# BenWalters_BB.net
KiCad netlist of a schematic drawn in EAGLE
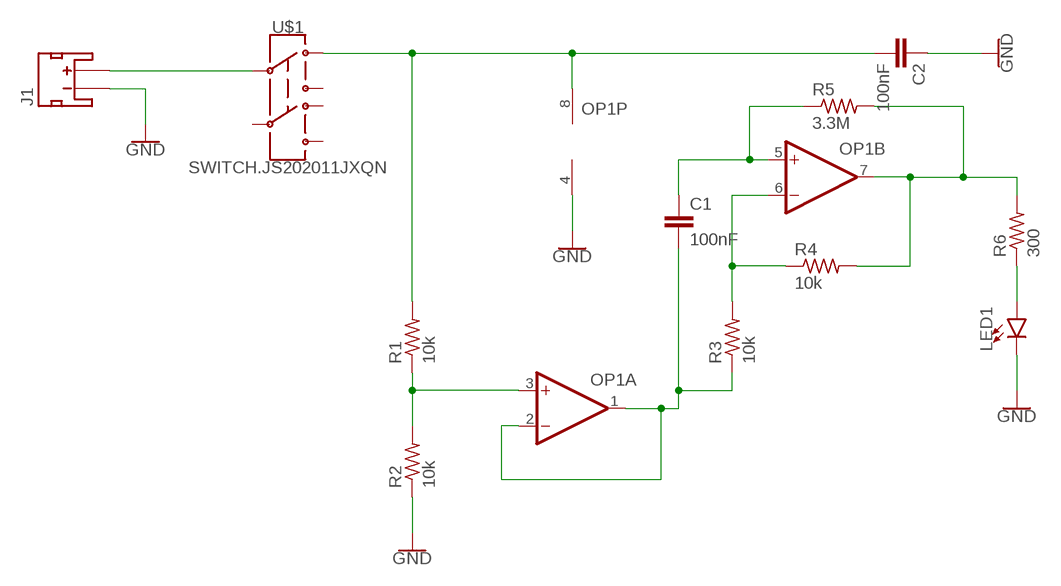
[diagram p0: schematic, sheet 1]

(export (version "E")
  (design (tool "Eeschema 10.0.6"))
  (components
    (comp (ref "C1")
      (value "100nF")
      (footprint "eagle-import:C0805")
      (libsource (lib "eagle-import") (part "CAPACITOR0805"))
    )
    (comp (ref "C2")
      (value "100nF")
      (footprint "eagle-import:C0805")
      (libsource (lib "eagle-import") (part "CAPACITOR0805"))
    )
    (comp (ref "J1")
      (value "3.7V")
      (footprint "eagle-import:JST-2-SMD")
      (libsource (lib "eagle-import") (part "JST_2MM_MALE"))
    )
    (comp (ref "LED1")
      (value "LED3MM")
      (footprint "eagle-import:LED_3MM")
      (libsource (lib "eagle-import") (part "LED3MM"))
    )
    (comp (ref "OP1")
      (value "OP-DUALRM")
      (footprint "eagle-import:MSOP08")
      (fields (field (name "MF") "ALTERA CORPORATION") (field (name "MPN") "AD8607ARMZ-REEL"))
      (libsource (lib "eagle-import") (part "OP-DUALRM"))
    )
    (comp (ref "R1")
      (value "10k")
      (footprint "eagle-import:R0805")
      (libsource (lib "eagle-import") (part "RESISTOR0805"))
    )
    (comp (ref "R2")
      (value "10k")
      (footprint "eagle-import:R0805")
      (libsource (lib "eagle-import") (part "RESISTOR0805"))
    )
    (comp (ref "R3")
      (value "10k")
      (footprint "eagle-import:R0805")
      (libsource (lib "eagle-import") (part "RESISTOR0805"))
    )
    (comp (ref "R4")
      (value "10k")
      (footprint "eagle-import:R0805")
      (libsource (lib "eagle-import") (part "RESISTOR0805"))
    )
    (comp (ref "R5")
      (value "3.3M")
      (footprint "eagle-import:R0805")
      (libsource (lib "eagle-import") (part "RESISTOR0805"))
    )
    (comp (ref "R6")
      (value "300")
      (footprint "eagle-import:R0805")
      (libsource (lib "eagle-import") (part "RESISTOR0805"))
    )
    (comp (ref "U$1")
      (value "SWITCH.JS202011JXQN")
      (footprint "eagle-import:SWITCH.00.THT")
      (libsource (lib "eagle-import") (part "SWITCH.JS202011JXQN"))
    )
  )
  (nets
    (net (code "1") (name "GND") (class "Default")
      (node (ref "C2") (pin "1") (pinfunction "1_1") (pintype "passive"))
      (node (ref "J1") (pin "1") (pinfunction "-_1") (pintype "bidirectional"))
      (node (ref "LED1") (pin "K") (pinfunction "C_K") (pintype "passive"))
      (node (ref "OP1") (pin "4") (pinfunction "V-_4") (pintype "power_in"))
      (node (ref "R2") (pin "1") (pinfunction "1_1") (pintype "passive"))
    )
    (net (code "2") (name "Net-(J1-+)") (class "Default")
      (node (ref "J1") (pin "2") (pinfunction "+_2") (pintype "bidirectional"))
      (node (ref "U$1") (pin "2") (pinfunction "2_2") (pintype "bidirectional"))
    )
    (net (code "3") (name "Net-(LED1-PadA)") (class "Default")
      (node (ref "LED1") (pin "A") (pinfunction "A_A") (pintype "passive"))
      (node (ref "R6") (pin "1") (pinfunction "1_1") (pintype "passive"))
    )
    (net (code "4") (name "Net-(OP1A-+IN)") (class "Default")
      (node (ref "OP1") (pin "3") (pinfunction "+IN_3") (pintype "input"))
      (node (ref "R1") (pin "1") (pinfunction "1_1") (pintype "passive"))
      (node (ref "R2") (pin "2") (pinfunction "2_2") (pintype "passive"))
    )
    (net (code "5") (name "Net-(OP1A--IN)") (class "Default")
      (node (ref "C1") (pin "2") (pinfunction "2_2") (pintype "passive"))
      (node (ref "OP1") (pin "1") (pinfunction "OUT_1") (pintype "output"))
      (node (ref "OP1") (pin "2") (pinfunction "-IN_2") (pintype "input"))
      (node (ref "R3") (pin "1") (pinfunction "1_1") (pintype "passive"))
    )
    (net (code "6") (name "Net-(OP1B-+IN)") (class "Default")
      (node (ref "C1") (pin "1") (pinfunction "1_1") (pintype "passive"))
      (node (ref "OP1") (pin "5") (pinfunction "+IN_5") (pintype "input"))
      (node (ref "R5") (pin "1") (pinfunction "1_1") (pintype "passive"))
    )
    (net (code "7") (name "Net-(OP1B--IN)") (class "Default")
      (node (ref "OP1") (pin "6") (pinfunction "-IN_6") (pintype "input"))
      (node (ref "R3") (pin "2") (pinfunction "2_2") (pintype "passive"))
      (node (ref "R4") (pin "1") (pinfunction "1_1") (pintype "passive"))
    )
    (net (code "8") (name "Net-(OP1B-OUT)") (class "Default")
      (node (ref "OP1") (pin "7") (pinfunction "OUT_7") (pintype "output"))
      (node (ref "R4") (pin "2") (pinfunction "2_2") (pintype "passive"))
      (node (ref "R5") (pin "2") (pinfunction "2_2") (pintype "passive"))
      (node (ref "R6") (pin "2") (pinfunction "2_2") (pintype "passive"))
    )
    (net (code "9") (name "Net-(OP1C-V+)") (class "Default")
      (node (ref "C2") (pin "2") (pinfunction "2_2") (pintype "passive"))
      (node (ref "OP1") (pin "8") (pinfunction "V+_8") (pintype "power_in"))
      (node (ref "R1") (pin "2") (pinfunction "2_2") (pintype "passive"))
      (node (ref "U$1") (pin "1") (pinfunction "1_1") (pintype "bidirectional"))
    )
    (net (code "10") (name "unconnected-(J1-PAD1-PadNC1)") (class "Default")
      (node (ref "J1") (pin "NC1") (pinfunction "PAD1_NC1") (pintype "bidirectional"))
    )
    (net (code "11") (name "unconnected-(J1-PAD2-PadNC2)") (class "Default")
      (node (ref "J1") (pin "NC2") (pinfunction "PAD2_NC2") (pintype "bidirectional"))
    )
    (net (code "12") (name "unconnected-(U$1-Pad3)") (class "Default")
      (node (ref "U$1") (pin "3") (pinfunction "3_3") (pintype "bidirectional"))
    )
    (net (code "13") (name "unconnected-(U$1-Pad5)") (class "Default")
      (node (ref "U$1") (pin "5") (pinfunction "5_5") (pintype "bidirectional"))
    )
    (net (code "14") (name "unconnected-(U$1-Pad6)") (class "Default")
      (node (ref "U$1") (pin "6") (pinfunction "6_6") (pintype "bidirectional"))
    )
    (net (code "15") (name "unconnected-(U$1-Pad7)") (class "Default")
      (node (ref "U$1") (pin "7") (pinfunction "7_7") (pintype "bidirectional"))
    )
  )
)
